# LT328v2.net
KiCad netlist of a schematic drawn in EAGLE
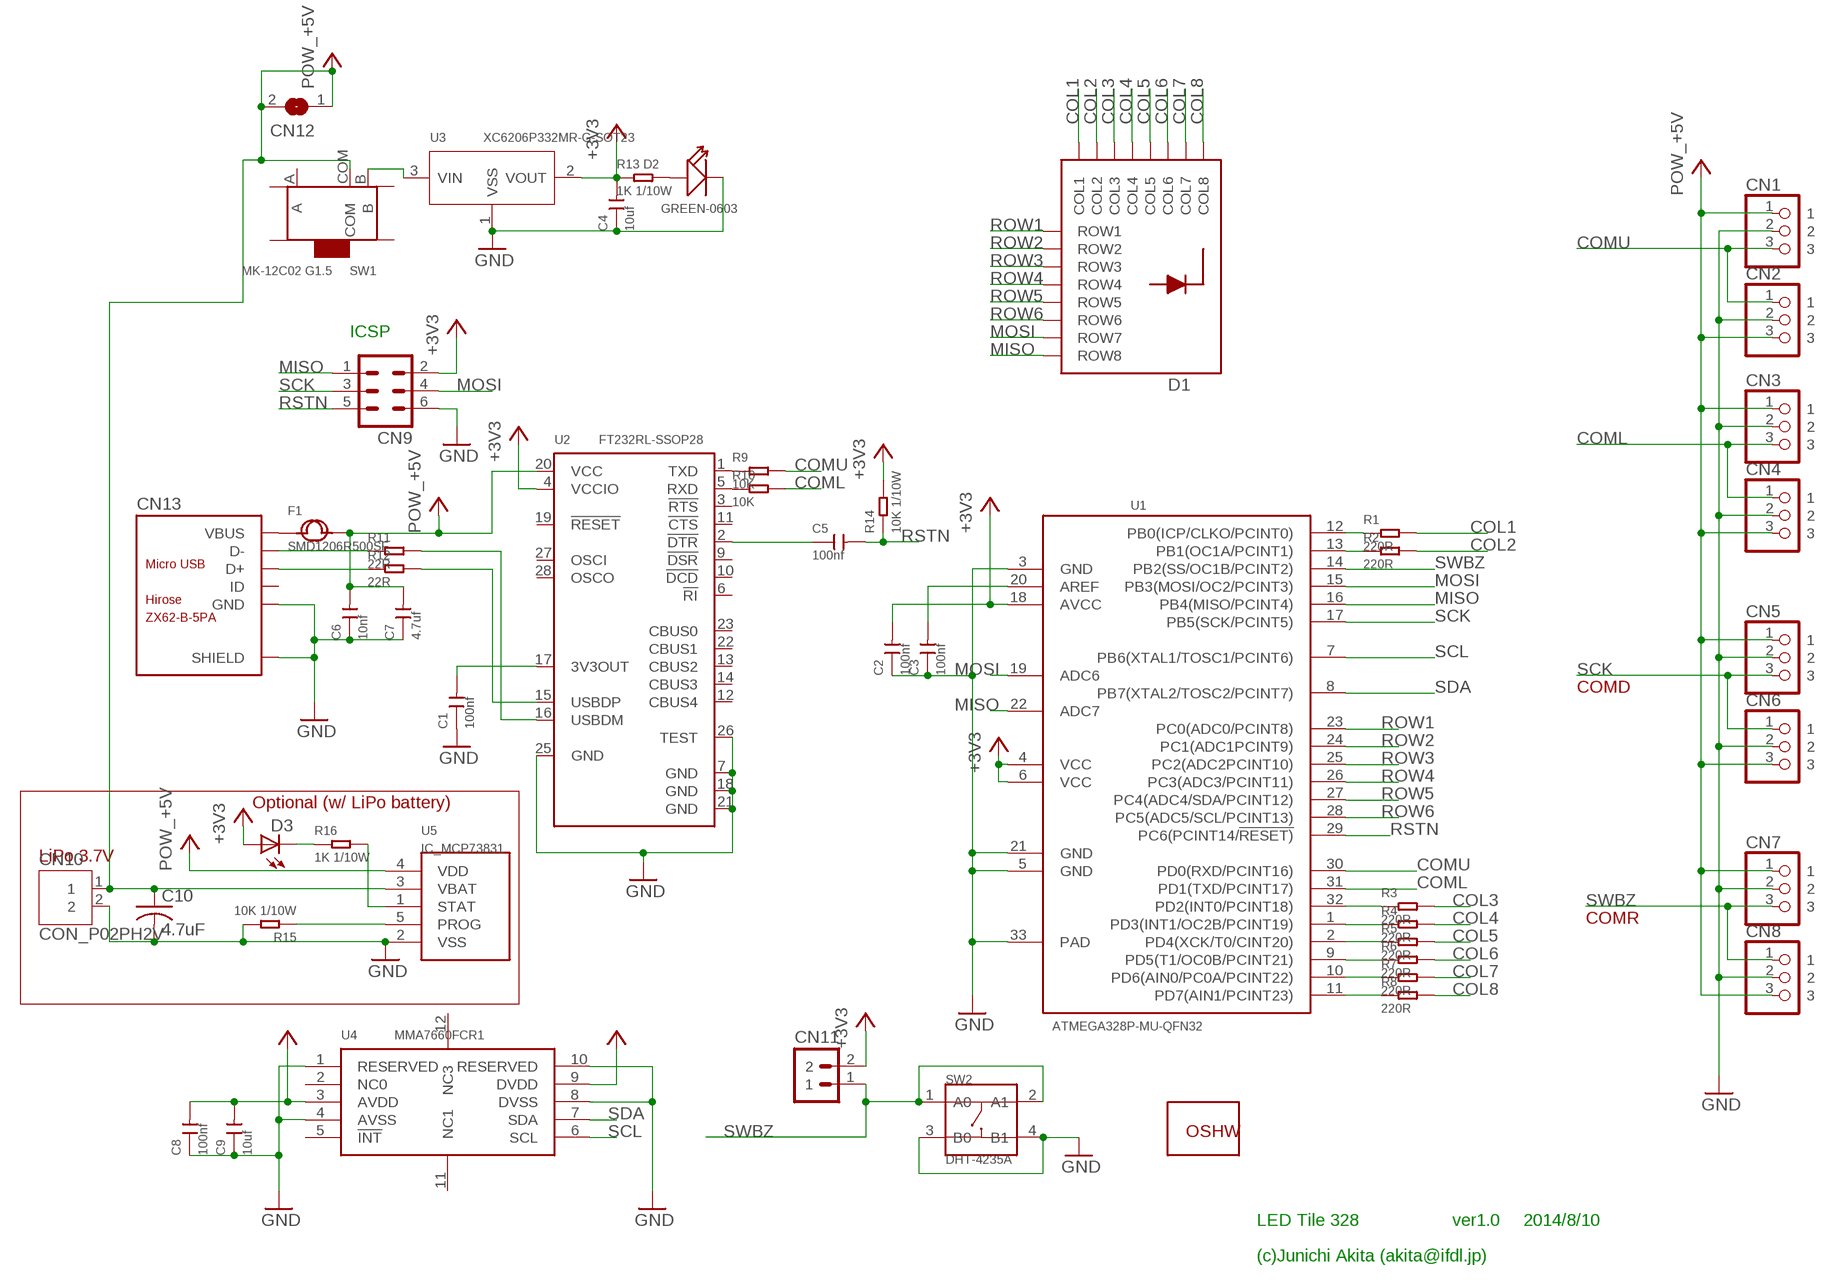
[diagram p0: schematic, sheet 1]

(export (version "E")
  (design (tool "Eeschema 10.0.6"))
  (components
    (comp (ref "C1")
      (value "100nf")
      (footprint "eagle-import:C0603")
      (fields (field (name "MPN") "CC0603KRX7R9BB104"))
      (libsource (lib "eagle-import") (part "CERAMIC-100NF-50V-10%-X7R(0603)"))
    )
    (comp (ref "C2")
      (value "100nf")
      (footprint "eagle-import:C0603")
      (fields (field (name "MPN") "CC0603KRX7R9BB104"))
      (libsource (lib "eagle-import") (part "CERAMIC-100NF-50V-10%-X7R(0603)"))
    )
    (comp (ref "C3")
      (value "100nf")
      (footprint "eagle-import:C0603")
      (fields (field (name "MPN") "CC0603KRX7R9BB104"))
      (libsource (lib "eagle-import") (part "CERAMIC-100NF-50V-10%-X7R(0603)"))
    )
    (comp (ref "C4")
      (value "10uf")
      (footprint "eagle-import:C0805")
      (fields (field (name "MPN") "CC0805ZKY5V6BB106"))
      (libsource (lib "eagle-import") (part "CERAMIC-10UF-10V-(-20%～+80%)-Y5V(0805)"))
    )
    (comp (ref "C5")
      (value "100nf")
      (footprint "eagle-import:C0603")
      (fields (field (name "MPN") "CC0603KRX7R9BB104"))
      (libsource (lib "eagle-import") (part "CERAMIC-100NF-50V-10%-X7R(0603)"))
    )
    (comp (ref "C6")
      (value "10nf")
      (footprint "eagle-import:C0603")
      (fields (field (name "MPN") "CC0603KRX7R9BB103"))
      (libsource (lib "eagle-import") (part "CERAMIC-10NF-50V-10%-X7R(0603)"))
    )
    (comp (ref "C7")
      (value "4.7uf")
      (footprint "eagle-import:C0603")
      (fields (field (name "MPN") "CC0603KRX5R6BB475"))
      (libsource (lib "eagle-import") (part "CERAMIC-4.7UF-10V-10%-X5R(0603)"))
    )
    (comp (ref "C8")
      (value "100nf")
      (footprint "eagle-import:C0603")
      (fields (field (name "MPN") "CC0603KRX7R9BB104"))
      (libsource (lib "eagle-import") (part "CERAMIC-100NF-50V-10%-X7R(0603)"))
    )
    (comp (ref "C9")
      (value "10uf")
      (footprint "eagle-import:C0805")
      (fields (field (name "MPN") "CC0805ZKY5V6BB106"))
      (libsource (lib "eagle-import") (part "CERAMIC-10UF-10V-(-20%～+80%)-Y5V(0805)"))
    )
    (comp (ref "C10")
      (value "4.7uF")
      (footprint "eagle-import:C0603")
      (libsource (lib "eagle-import") (part "C-USC0603"))
    )
    (comp (ref "CN1")
      (value "CON_PINHD-1X3R")
      (footprint "eagle-import:1X03R")
      (libsource (lib "eagle-import") (part "CON_PINHD-1X3R"))
    )
    (comp (ref "CN2")
      (value "CON_PINHD-1X3R")
      (footprint "eagle-import:1X03R")
      (libsource (lib "eagle-import") (part "CON_PINHD-1X3R"))
    )
    (comp (ref "CN3")
      (value "CON_PINHD-1X3R")
      (footprint "eagle-import:1X03R")
      (libsource (lib "eagle-import") (part "CON_PINHD-1X3R"))
    )
    (comp (ref "CN4")
      (value "CON_PINHD-1X3R")
      (footprint "eagle-import:1X03R")
      (libsource (lib "eagle-import") (part "CON_PINHD-1X3R"))
    )
    (comp (ref "CN5")
      (value "CON_PINHD-1X3R")
      (footprint "eagle-import:1X03R")
      (libsource (lib "eagle-import") (part "CON_PINHD-1X3R"))
    )
    (comp (ref "CN6")
      (value "CON_PINHD-1X3R")
      (footprint "eagle-import:1X03R")
      (libsource (lib "eagle-import") (part "CON_PINHD-1X3R"))
    )
    (comp (ref "CN7")
      (value "CON_PINHD-1X3R")
      (footprint "eagle-import:1X03R")
      (libsource (lib "eagle-import") (part "CON_PINHD-1X3R"))
    )
    (comp (ref "CN8")
      (value "CON_PINHD-1X3R")
      (footprint "eagle-import:1X03R")
      (libsource (lib "eagle-import") (part "CON_PINHD-1X3R"))
    )
    (comp (ref "CN9")
      (value "MA03-2")
      (footprint "eagle-import:MA03-2")
      (libsource (lib "eagle-import") (part "MA03-2"))
    )
    (comp (ref "CN10")
      (value "CON_P02PH2V")
      (footprint "eagle-import:JST-PH2")
      (libsource (lib "eagle-import") (part "CON_P02PH2V"))
    )
    (comp (ref "CN11")
      (value "CON_PINHD-1X2PTH")
      (footprint "eagle-import:SPARKFUN_1X02")
      (libsource (lib "eagle-import") (part "CON_PINHD-1X2PTH"))
    )
    (comp (ref "CN12")
      (value "JUMPER_SJ")
      (footprint "eagle-import:JUMPER_SJ")
      (libsource (lib "eagle-import") (part "JUMPER_SJ"))
    )
    (comp (ref "CN13")
      (value "ZX62-B-5PA")
      (footprint "eagle-import:MICRO-USB5+6P-SMD-0.65-AB")
      (libsource (lib "eagle-import") (part "MICRO-USB-SMD(ZX62-B-5PA)"))
    )
    (comp (ref "D1")
      (value "LED_OSL641501BRA")
      (footprint "eagle-import:TOM-1588BH")
      (libsource (lib "eagle-import") (part "LED_OSL641501BRA"))
    )
    (comp (ref "D2")
      (value "GREEN-0603")
      (footprint "eagle-import:LED-0603")
      (fields (field (name "MPN") "19-217-G7C-AN1P2-3T"))
      (libsource (lib "eagle-import") (part "SMD-LED-CLEAR-GREEN(0603)"))
    )
    (comp (ref "D3")
      (value "LED0603")
      (footprint "eagle-import:SPARKFUN_LED-0603")
      (libsource (lib "eagle-import") (part "LED0603"))
    )
    (comp (ref "F1")
      (value "SMD1206R500SF")
      (footprint "eagle-import:F1206")
      (libsource (lib "eagle-import") (part "SMD-PPTC-500MA(1206)"))
    )
    (comp (ref "GOLD_ORB_SM1")
      (value "OSHWLOGO_GOLD_ORB_SM")
      (footprint "eagle-import:OSHW2")
      (libsource (lib "eagle-import") (part "OSHWLOGO_GOLD_ORB_SM"))
    )
    (comp (ref "R1")
      (value "220R")
      (footprint "eagle-import:R0603")
      (fields (field (name "MPN") "RC0603JR-07220RL"))
      (libsource (lib "eagle-import") (part "SMD-RES-220R-5%-1/10W(0603)"))
    )
    (comp (ref "R2")
      (value "220R")
      (footprint "eagle-import:R0603")
      (fields (field (name "MPN") "RC0603JR-07220RL"))
      (libsource (lib "eagle-import") (part "SMD-RES-220R-5%-1/10W(0603)"))
    )
    (comp (ref "R3")
      (value "220R")
      (footprint "eagle-import:R0603")
      (fields (field (name "MPN") "RC0603JR-07220RL"))
      (libsource (lib "eagle-import") (part "SMD-RES-220R-5%-1/10W(0603)"))
    )
    (comp (ref "R4")
      (value "220R")
      (footprint "eagle-import:R0603")
      (fields (field (name "MPN") "RC0603JR-07220RL"))
      (libsource (lib "eagle-import") (part "SMD-RES-220R-5%-1/10W(0603)"))
    )
    (comp (ref "R5")
      (value "220R")
      (footprint "eagle-import:R0603")
      (fields (field (name "MPN") "RC0603JR-07220RL"))
      (libsource (lib "eagle-import") (part "SMD-RES-220R-5%-1/10W(0603)"))
    )
    (comp (ref "R6")
      (value "220R")
      (footprint "eagle-import:R0603")
      (fields (field (name "MPN") "RC0603JR-07220RL"))
      (libsource (lib "eagle-import") (part "SMD-RES-220R-5%-1/10W(0603)"))
    )
    (comp (ref "R7")
      (value "220R")
      (footprint "eagle-import:R0603")
      (fields (field (name "MPN") "RC0603JR-07220RL"))
      (libsource (lib "eagle-import") (part "SMD-RES-220R-5%-1/10W(0603)"))
    )
    (comp (ref "R8")
      (value "220R")
      (footprint "eagle-import:R0603")
      (fields (field (name "MPN") "RC0603JR-07220RL"))
      (libsource (lib "eagle-import") (part "SMD-RES-220R-5%-1/10W(0603)"))
    )
    (comp (ref "R9")
      (value "10K")
      (footprint "eagle-import:R0603")
      (fields (field (name "MPN") "RC0603FR-0710KL"))
      (libsource (lib "eagle-import") (part "SMD-RES-10K-1%-1/10W(0603)"))
    )
    (comp (ref "R10")
      (value "10K")
      (footprint "eagle-import:R0603")
      (fields (field (name "MPN") "RC0603FR-0710KL"))
      (libsource (lib "eagle-import") (part "SMD-RES-10K-1%-1/10W(0603)"))
    )
    (comp (ref "R11")
      (value "22R")
      (footprint "eagle-import:R0603")
      (fields (field (name "MPN") "RC0603JR-0722RL"))
      (libsource (lib "eagle-import") (part "SMD-RES-22R-5%-1/10W(0603)"))
    )
    (comp (ref "R12")
      (value "22R")
      (footprint "eagle-import:R0603")
      (fields (field (name "MPN") "RC0603JR-0722RL"))
      (libsource (lib "eagle-import") (part "SMD-RES-22R-5%-1/10W(0603)"))
    )
    (comp (ref "R13")
      (value "1K 1/10W")
      (footprint "eagle-import:R0603")
      (fields (field (name "MPN") "RC0603JR-071KL"))
      (libsource (lib "eagle-import") (part "SMD-RES-1K-5%-1/10W(0603)"))
    )
    (comp (ref "R14")
      (value "10K 1/10W")
      (footprint "eagle-import:R0603")
      (fields (field (name "MPN") "RC0603JR-0710KL"))
      (libsource (lib "eagle-import") (part "SMD-RES-10K-5%-1/10W(0603)"))
    )
    (comp (ref "R15")
      (value "10K 1/10W")
      (footprint "eagle-import:R0603")
      (fields (field (name "MPN") "RC0603JR-0710KL"))
      (libsource (lib "eagle-import") (part "SMD-RES-10K-5%-1/10W(0603)"))
    )
    (comp (ref "R16")
      (value "1K 1/10W")
      (footprint "eagle-import:R0603")
      (fields (field (name "MPN") "RC0603JR-071KL"))
      (libsource (lib "eagle-import") (part "SMD-RES-1K-5%-1/10W(0603)"))
    )
    (comp (ref "SW1")
      (value "MK-12C02 G1.5")
      (footprint "eagle-import:SW7-SMD-L6.7X2.7X3.2MM")
      (libsource (lib "eagle-import") (part "SMD-TOGGLE-SWITCH-ON-ON(3+4P-6.7X2.7MM)"))
    )
    (comp (ref "SW2")
      (value "DHT-4235A")
      (footprint "eagle-import:SW4-SMD-4.2X3.2X2.5MM")
      (libsource (lib "eagle-import") (part "SMD-BUTTON-TOP-DHT-4235A(4P-4.2X3.2MM)"))
    )
    (comp (ref "U1")
      (value "ATMEGA328P-MU-QFN32")
      (footprint "eagle-import:QFN32G-0.5-5X5MM")
      (fields (field (name "MPN") "ATMEGA328P-MU"))
      (libsource (lib "eagle-import") (part "MCU-ATMEGA328P-MU(QFN32)"))
    )
    (comp (ref "U2")
      (value "FT232RL-SSOP28")
      (footprint "eagle-import:SSOP28-0.65-10.2X5.2MM")
      (fields (field (name "MPN") "FT232RL"))
      (libsource (lib "eagle-import") (part "INTERFACE-FT232RL(SSOP28)"))
    )
    (comp (ref "U3")
      (value "XC6206P332MR-G-SOT23")
      (footprint "eagle-import:SOT-23")
      (fields (field (name "MPN") "XC6206P332MR-G"))
      (libsource (lib "eagle-import") (part "PMIC-LDO-XC6206P332MR-G(SOT23)"))
    )
    (comp (ref "U4")
      (value "MMA7660FCR1")
      (footprint "eagle-import:DFN10-0.5-3.0X3.0MM")
      (libsource (lib "eagle-import") (part "MOTION/POSITION-MMA7660FCR1(DFN10)"))
    )
    (comp (ref "U5")
      (value "IC_MCP73831")
      (footprint "eagle-import:SOT23-5L")
      (libsource (lib "eagle-import") (part "IC_MCP73831"))
    )
  )
  (nets
    (net (code "1") (name "+3V3") (class "Default")
      (node (ref "C2") (pin "2") (pinfunction "2_2") (pintype "passive"))
      (node (ref "C4") (pin "2") (pinfunction "2_2") (pintype "passive"))
      (node (ref "C8") (pin "2") (pinfunction "2_2") (pintype "passive"))
      (node (ref "C9") (pin "2") (pinfunction "2_2") (pintype "passive"))
      (node (ref "CN11") (pin "2") (pinfunction "2_2") (pintype "passive"))
      (node (ref "CN9") (pin "2") (pinfunction "2_2") (pintype "passive"))
      (node (ref "D3") (pin "A") (pinfunction "A_A") (pintype "passive"))
      (node (ref "R13") (pin "1") (pinfunction "1_1") (pintype "passive"))
      (node (ref "R14") (pin "2") (pinfunction "2_2") (pintype "passive"))
      (node (ref "U1") (pin "18") (pinfunction "AVCC_18") (pintype "bidirectional"))
      (node (ref "U1") (pin "4") (pinfunction "VCC_4") (pintype "bidirectional"))
      (node (ref "U1") (pin "6") (pinfunction "VCC_6") (pintype "bidirectional"))
      (node (ref "U2") (pin "4") (pinfunction "VCCIO_4") (pintype "input"))
      (node (ref "U3") (pin "2") (pinfunction "VOUT_2") (pintype "output"))
      (node (ref "U4") (pin "3") (pinfunction "AVDD_3") (pintype "power_in"))
      (node (ref "U4") (pin "9") (pinfunction "DVDD_9") (pintype "bidirectional"))
    )
    (net (code "2") (name "/COL1") (class "Default")
      (node (ref "D1") (pin "P$13") (pinfunction "COL1_P$13") (pintype "bidirectional"))
      (node (ref "R1") (pin "2") (pinfunction "2_2") (pintype "passive"))
    )
    (net (code "3") (name "/COL2") (class "Default")
      (node (ref "D1") (pin "P$3") (pinfunction "COL2_P$3") (pintype "bidirectional"))
      (node (ref "R2") (pin "2") (pinfunction "2_2") (pintype "passive"))
    )
    (net (code "4") (name "/COL3") (class "Default")
      (node (ref "D1") (pin "P$4") (pinfunction "COL3_P$4") (pintype "bidirectional"))
      (node (ref "R3") (pin "2") (pinfunction "2_2") (pintype "passive"))
    )
    (net (code "5") (name "/COL4") (class "Default")
      (node (ref "D1") (pin "P$10") (pinfunction "COL4_P$10") (pintype "bidirectional"))
      (node (ref "R4") (pin "2") (pinfunction "2_2") (pintype "passive"))
    )
    (net (code "6") (name "/COL5") (class "Default")
      (node (ref "D1") (pin "P$6") (pinfunction "COL5_P$6") (pintype "bidirectional"))
      (node (ref "R5") (pin "2") (pinfunction "2_2") (pintype "passive"))
    )
    (net (code "7") (name "/COL6") (class "Default")
      (node (ref "D1") (pin "P$11") (pinfunction "COL6_P$11") (pintype "bidirectional"))
      (node (ref "R6") (pin "2") (pinfunction "2_2") (pintype "passive"))
    )
    (net (code "8") (name "/COL7") (class "Default")
      (node (ref "D1") (pin "P$15") (pinfunction "COL7_P$15") (pintype "bidirectional"))
      (node (ref "R7") (pin "2") (pinfunction "2_2") (pintype "passive"))
    )
    (net (code "9") (name "/COL8") (class "Default")
      (node (ref "D1") (pin "P$16") (pinfunction "COL8_P$16") (pintype "bidirectional"))
      (node (ref "R8") (pin "2") (pinfunction "2_2") (pintype "passive"))
    )
    (net (code "10") (name "/COML") (class "Default")
      (node (ref "CN3") (pin "3") (pinfunction "3_3") (pintype "passive"))
      (node (ref "CN4") (pin "1") (pinfunction "1_1") (pintype "passive"))
      (node (ref "R10") (pin "2") (pinfunction "2_2") (pintype "passive"))
      (node (ref "U1") (pin "31") (pinfunction "PD1(TXD/PCINT17)_31") (pintype "bidirectional"))
    )
    (net (code "11") (name "/COMU") (class "Default")
      (node (ref "CN1") (pin "3") (pinfunction "3_3") (pintype "passive"))
      (node (ref "CN2") (pin "1") (pinfunction "1_1") (pintype "passive"))
      (node (ref "R9") (pin "2") (pinfunction "2_2") (pintype "passive"))
      (node (ref "U1") (pin "30") (pinfunction "PD0(RXD/PCINT16)_30") (pintype "bidirectional"))
    )
    (net (code "12") (name "/MISO") (class "Default")
      (node (ref "CN9") (pin "1") (pinfunction "1_1") (pintype "passive"))
      (node (ref "D1") (pin "P$5") (pinfunction "ROW8_P$5") (pintype "bidirectional"))
      (node (ref "U1") (pin "16") (pinfunction "PB4(MISO/PCINT4)_16") (pintype "bidirectional"))
      (node (ref "U1") (pin "22") (pinfunction "ADC7_22") (pintype "bidirectional"))
    )
    (net (code "13") (name "/MOSI") (class "Default")
      (node (ref "CN9") (pin "4") (pinfunction "4_4") (pintype "passive"))
      (node (ref "D1") (pin "P$2") (pinfunction "ROW7_P$2") (pintype "bidirectional"))
      (node (ref "U1") (pin "15") (pinfunction "PB3(MOSI/OC2/PCINT3)_15") (pintype "bidirectional"))
      (node (ref "U1") (pin "19") (pinfunction "ADC6_19") (pintype "bidirectional"))
    )
    (net (code "14") (name "/ROW1") (class "Default")
      (node (ref "D1") (pin "P$9") (pinfunction "ROW1_P$9") (pintype "bidirectional"))
      (node (ref "U1") (pin "23") (pinfunction "PC0(ADC0/PCINT8)_23") (pintype "bidirectional"))
    )
    (net (code "15") (name "/ROW2") (class "Default")
      (node (ref "D1") (pin "P$14") (pinfunction "ROW2_P$14") (pintype "bidirectional"))
      (node (ref "U1") (pin "24") (pinfunction "PC1(ADC1PCINT9)_24") (pintype "bidirectional"))
    )
    (net (code "16") (name "/ROW3") (class "Default")
      (node (ref "D1") (pin "P$8") (pinfunction "ROW3_P$8") (pintype "bidirectional"))
      (node (ref "U1") (pin "25") (pinfunction "PC2(ADC2PCINT10)_25") (pintype "bidirectional"))
    )
    (net (code "17") (name "/ROW4") (class "Default")
      (node (ref "D1") (pin "P$12") (pinfunction "ROW4_P$12") (pintype "bidirectional"))
      (node (ref "U1") (pin "26") (pinfunction "PC3(ADC3/PCINT11)_26") (pintype "bidirectional"))
    )
    (net (code "18") (name "/ROW5") (class "Default")
      (node (ref "D1") (pin "P$1") (pinfunction "ROW5_P$1") (pintype "bidirectional"))
      (node (ref "U1") (pin "27") (pinfunction "PC4(ADC4/SDA/PCINT12)_27") (pintype "bidirectional"))
    )
    (net (code "19") (name "/ROW6") (class "Default")
      (node (ref "D1") (pin "P$7") (pinfunction "ROW6_P$7") (pintype "bidirectional"))
      (node (ref "U1") (pin "28") (pinfunction "PC5(ADC5/SCL/PCINT13)_28") (pintype "bidirectional"))
    )
    (net (code "20") (name "/RSTN") (class "Default")
      (node (ref "C5") (pin "2") (pinfunction "2_2") (pintype "passive"))
      (node (ref "CN9") (pin "5") (pinfunction "5_5") (pintype "passive"))
      (node (ref "R14") (pin "1") (pinfunction "1_1") (pintype "passive"))
      (node (ref "U1") (pin "29") (pinfunction "PC6(PCINT14/~{RESET})_29") (pintype "bidirectional"))
    )
    (net (code "21") (name "/SCK") (class "Default")
      (node (ref "CN5") (pin "3") (pinfunction "3_3") (pintype "passive"))
      (node (ref "CN6") (pin "1") (pinfunction "1_1") (pintype "passive"))
      (node (ref "CN9") (pin "3") (pinfunction "3_3") (pintype "passive"))
      (node (ref "U1") (pin "17") (pinfunction "PB5(SCK/PCINT5)_17") (pintype "bidirectional"))
    )
    (net (code "22") (name "/SCL") (class "Default")
      (node (ref "U1") (pin "7") (pinfunction "PB6(XTAL1/TOSC1/PCINT6)_7") (pintype "bidirectional"))
      (node (ref "U4") (pin "6") (pinfunction "SCL_6") (pintype "bidirectional"))
    )
    (net (code "23") (name "/SDA") (class "Default")
      (node (ref "U1") (pin "8") (pinfunction "PB7(XTAL2/TOSC2/PCINT7)_8") (pintype "bidirectional"))
      (node (ref "U4") (pin "7") (pinfunction "SDA_7") (pintype "bidirectional"))
    )
    (net (code "24") (name "/SWBZ") (class "Default")
      (node (ref "CN11") (pin "1") (pinfunction "1_1") (pintype "passive"))
      (node (ref "CN7") (pin "3") (pinfunction "3_3") (pintype "passive"))
      (node (ref "CN8") (pin "1") (pinfunction "1_1") (pintype "passive"))
      (node (ref "SW2") (pin "1") (pinfunction "A0_1") (pintype "bidirectional"))
      (node (ref "SW2") (pin "2") (pinfunction "A1_2") (pintype "bidirectional"))
      (node (ref "U1") (pin "14") (pinfunction "PB2(SS/OC1B/PCINT2)_14") (pintype "bidirectional"))
    )
    (net (code "25") (name "GND") (class "Default")
      (node (ref "C1") (pin "1") (pinfunction "1_1") (pintype "passive"))
      (node (ref "C10") (pin "2") (pinfunction "2_2") (pintype "passive"))
      (node (ref "C2") (pin "1") (pinfunction "1_1") (pintype "passive"))
      (node (ref "C3") (pin "1") (pinfunction "1_1") (pintype "passive"))
      (node (ref "C4") (pin "1") (pinfunction "1_1") (pintype "passive"))
      (node (ref "C6") (pin "1") (pinfunction "1_1") (pintype "passive"))
      (node (ref "C7") (pin "1") (pinfunction "1_1") (pintype "passive"))
      (node (ref "C8") (pin "1") (pinfunction "1_1") (pintype "passive"))
      (node (ref "C9") (pin "1") (pinfunction "1_1") (pintype "passive"))
      (node (ref "CN1") (pin "2") (pinfunction "2_2") (pintype "passive"))
      (node (ref "CN10") (pin "2") (pinfunction "2_2") (pintype "passive"))
      (node (ref "CN13") (pin "5") (pinfunction "GND_5") (pintype "power_in"))
      (node (ref "CN13") (pin "P1") (pinfunction "SHIELD_P1") (pintype "power_in"))
      (node (ref "CN13") (pin "P2") (pinfunction "SHIELD_P2") (pintype "power_in"))
      (node (ref "CN13") (pin "P3") (pinfunction "SHIELD_P3") (pintype "power_in"))
      (node (ref "CN13") (pin "P4") (pinfunction "SHIELD_P4") (pintype "power_in"))
      (node (ref "CN13") (pin "P5") (pinfunction "SHIELD_P5") (pintype "power_in"))
      (node (ref "CN13") (pin "P6") (pinfunction "SHIELD_P6") (pintype "power_in"))
      (node (ref "CN2") (pin "2") (pinfunction "2_2") (pintype "passive"))
      (node (ref "CN3") (pin "2") (pinfunction "2_2") (pintype "passive"))
      (node (ref "CN4") (pin "2") (pinfunction "2_2") (pintype "passive"))
      (node (ref "CN5") (pin "2") (pinfunction "2_2") (pintype "passive"))
      (node (ref "CN6") (pin "2") (pinfunction "2_2") (pintype "passive"))
      (node (ref "CN7") (pin "2") (pinfunction "2_2") (pintype "passive"))
      (node (ref "CN8") (pin "2") (pinfunction "2_2") (pintype "passive"))
      (node (ref "CN9") (pin "6") (pinfunction "6_6") (pintype "passive"))
      (node (ref "D2") (pin "-") (pinfunction "-_-") (pintype "passive"))
      (node (ref "R15") (pin "2") (pinfunction "2_2") (pintype "passive"))
      (node (ref "SW2") (pin "3") (pinfunction "B0_3") (pintype "bidirectional"))
      (node (ref "SW2") (pin "4") (pinfunction "B1_4") (pintype "bidirectional"))
      (node (ref "U1") (pin "21") (pinfunction "GND_21") (pintype "bidirectional"))
      (node (ref "U1") (pin "3") (pinfunction "GND_3") (pintype "bidirectional"))
      (node (ref "U1") (pin "33") (pinfunction "PAD_33") (pintype "bidirectional"))
      (node (ref "U1") (pin "5") (pinfunction "GND_5") (pintype "bidirectional"))
      (node (ref "U2") (pin "18") (pinfunction "GND_18") (pintype "input"))
      (node (ref "U2") (pin "21") (pinfunction "GND_21") (pintype "input"))
      (node (ref "U2") (pin "25") (pinfunction "GND_25") (pintype "input"))
      (node (ref "U2") (pin "26") (pinfunction "TEST_26") (pintype "input"))
      (node (ref "U2") (pin "7") (pinfunction "GND_7") (pintype "input"))
      (node (ref "U3") (pin "1") (pinfunction "VSS_1") (pintype "power_in"))
      (node (ref "U4") (pin "1") (pinfunction "RESERVED_1") (pintype "bidirectional"))
      (node (ref "U4") (pin "10") (pinfunction "RESERVED_10") (pintype "bidirectional"))
      (node (ref "U4") (pin "4") (pinfunction "AVSS_4") (pintype "power_in"))
      (node (ref "U4") (pin "8") (pinfunction "DVSS_8") (pintype "bidirectional"))
      (node (ref "U5") (pin "2") (pinfunction "VSS_2") (pintype "bidirectional"))
    )
    (net (code "26") (name "Net-(CN13-D+)") (class "Default")
      (node (ref "CN13") (pin "3") (pinfunction "D+_3") (pintype "bidirectional"))
      (node (ref "R12") (pin "1") (pinfunction "1_1") (pintype "passive"))
    )
    (net (code "27") (name "Net-(CN13-D-)") (class "Default")
      (node (ref "CN13") (pin "2") (pinfunction "D-_2") (pintype "bidirectional"))
      (node (ref "R11") (pin "1") (pinfunction "1_1") (pintype "passive"))
    )
    (net (code "28") (name "Net-(CN13-VBUS)") (class "Default")
      (node (ref "CN13") (pin "1") (pinfunction "VBUS_1") (pintype "power_in"))
      (node (ref "F1") (pin "1") (pinfunction "1_1") (pintype "bidirectional"))
    )
    (net (code "29") (name "Net-(D2-Pad+)") (class "Default")
      (node (ref "D2") (pin "+") (pinfunction "+_+") (pintype "passive"))
      (node (ref "R13") (pin "2") (pinfunction "2_2") (pintype "passive"))
    )
    (net (code "30") (name "Net-(D3-PadC)") (class "Default")
      (node (ref "D3") (pin "C") (pinfunction "C_C") (pintype "passive"))
      (node (ref "R16") (pin "1") (pinfunction "1_1") (pintype "passive"))
    )
    (net (code "31") (name "Net-(U1-AREF)") (class "Default")
      (node (ref "C3") (pin "2") (pinfunction "2_2") (pintype "passive"))
      (node (ref "U1") (pin "20") (pinfunction "AREF_20") (pintype "bidirectional"))
    )
    (net (code "32") (name "Net-(U1-PB0(ICP{slash}CLKO{slash}PCINT0))") (class "Default")
      (node (ref "R1") (pin "1") (pinfunction "1_1") (pintype "passive"))
      (node (ref "U1") (pin "12") (pinfunction "PB0(ICP/CLKO/PCINT0)_12") (pintype "bidirectional"))
    )
    (net (code "33") (name "Net-(U1-PB1(OC1A{slash}PCINT1))") (class "Default")
      (node (ref "R2") (pin "1") (pinfunction "1_1") (pintype "passive"))
      (node (ref "U1") (pin "13") (pinfunction "PB1(OC1A/PCINT1)_13") (pintype "bidirectional"))
    )
    (net (code "34") (name "Net-(U1-PD2(INT0{slash}PCINT18))") (class "Default")
      (node (ref "R3") (pin "1") (pinfunction "1_1") (pintype "passive"))
      (node (ref "U1") (pin "32") (pinfunction "PD2(INT0/PCINT18)_32") (pintype "bidirectional"))
    )
    (net (code "35") (name "Net-(U1-PD3(INT1{slash}OC2B{slash}PCINT19))") (class "Default")
      (node (ref "R4") (pin "1") (pinfunction "1_1") (pintype "passive"))
      (node (ref "U1") (pin "1") (pinfunction "PD3(INT1/OC2B/PCINT19)_1") (pintype "bidirectional"))
    )
    (net (code "36") (name "Net-(U1-PD4(XCK{slash}T0{slash}CINT20))") (class "Default")
      (node (ref "R5") (pin "1") (pinfunction "1_1") (pintype "passive"))
      (node (ref "U1") (pin "2") (pinfunction "PD4(XCK/T0/CINT20)_2") (pintype "bidirectional"))
    )
    (net (code "37") (name "Net-(U1-PD5(T1{slash}OC0B{slash}PCINT21))") (class "Default")
      (node (ref "R6") (pin "1") (pinfunction "1_1") (pintype "passive"))
      (node (ref "U1") (pin "9") (pinfunction "PD5(T1/OC0B/PCINT21)_9") (pintype "bidirectional"))
    )
    (net (code "38") (name "Net-(U1-PD6(AIN0{slash}PC0A{slash}PCINT22))") (class "Default")
      (node (ref "R7") (pin "1") (pinfunction "1_1") (pintype "passive"))
      (node (ref "U1") (pin "10") (pinfunction "PD6(AIN0/PC0A/PCINT22)_10") (pintype "bidirectional"))
    )
    (net (code "39") (name "Net-(U1-PD7(AIN1{slash}PCINT23))") (class "Default")
      (node (ref "R8") (pin "1") (pinfunction "1_1") (pintype "passive"))
      (node (ref "U1") (pin "11") (pinfunction "PD7(AIN1/PCINT23)_11") (pintype "bidirectional"))
    )
    (net (code "40") (name "Net-(U2-3V3OUT)") (class "Default")
      (node (ref "C1") (pin "2") (pinfunction "2_2") (pintype "passive"))
      (node (ref "U2") (pin "17") (pinfunction "3V3OUT_17") (pintype "input"))
    )
    (net (code "41") (name "Net-(U2-RXD)") (class "Default")
      (node (ref "R10") (pin "1") (pinfunction "1_1") (pintype "passive"))
      (node (ref "U2") (pin "5") (pinfunction "RXD_5") (pintype "input"))
    )
    (net (code "42") (name "Net-(U2-TXD)") (class "Default")
      (node (ref "R9") (pin "1") (pinfunction "1_1") (pintype "passive"))
      (node (ref "U2") (pin "1") (pinfunction "TXD_1") (pintype "input"))
    )
    (net (code "43") (name "Net-(U2-USBDM)") (class "Default")
      (node (ref "R11") (pin "2") (pinfunction "2_2") (pintype "passive"))
      (node (ref "U2") (pin "16") (pinfunction "USBDM_16") (pintype "input"))
    )
    (net (code "44") (name "Net-(U2-USBDP)") (class "Default")
      (node (ref "R12") (pin "2") (pinfunction "2_2") (pintype "passive"))
      (node (ref "U2") (pin "15") (pinfunction "USBDP_15") (pintype "input"))
    )
    (net (code "45") (name "Net-(U2-~{DTR})") (class "Default")
      (node (ref "C5") (pin "1") (pinfunction "1_1") (pintype "passive"))
      (node (ref "U2") (pin "2") (pinfunction "~{DTR}_2") (pintype "input"))
    )
    (net (code "46") (name "Net-(U3-VIN)") (class "Default")
      (node (ref "SW1") (pin "B") (pinfunction "B_B") (pintype "bidirectional"))
      (node (ref "U3") (pin "3") (pinfunction "VIN_3") (pintype "input"))
    )
    (net (code "47") (name "Net-(U5-PROG)") (class "Default")
      (node (ref "R15") (pin "1") (pinfunction "1_1") (pintype "passive"))
      (node (ref "U5") (pin "5") (pinfunction "PROG_5") (pintype "bidirectional"))
    )
    (net (code "48") (name "Net-(U5-STAT)") (class "Default")
      (node (ref "R16") (pin "2") (pinfunction "2_2") (pintype "passive"))
      (node (ref "U5") (pin "1") (pinfunction "STAT_1") (pintype "bidirectional"))
    )
    (net (code "49") (name "POW_+5V") (class "Default")
      (node (ref "C10") (pin "1") (pinfunction "1_1") (pintype "passive"))
      (node (ref "C6") (pin "2") (pinfunction "2_2") (pintype "passive"))
      (node (ref "C7") (pin "2") (pinfunction "2_2") (pintype "passive"))
      (node (ref "CN1") (pin "1") (pinfunction "1_1") (pintype "passive"))
      (node (ref "CN10") (pin "1") (pinfunction "1_1") (pintype "passive"))
      (node (ref "CN12") (pin "1") (pinfunction "1_1") (pintype "passive"))
      (node (ref "CN12") (pin "2") (pinfunction "2_2") (pintype "passive"))
      (node (ref "CN2") (pin "3") (pinfunction "3_3") (pintype "passive"))
      (node (ref "CN3") (pin "1") (pinfunction "1_1") (pintype "passive"))
      (node (ref "CN4") (pin "3") (pinfunction "3_3") (pintype "passive"))
      (node (ref "CN5") (pin "1") (pinfunction "1_1") (pintype "passive"))
      (node (ref "CN6") (pin "3") (pinfunction "3_3") (pintype "passive"))
      (node (ref "CN7") (pin "1") (pinfunction "1_1") (pintype "passive"))
      (node (ref "CN8") (pin "3") (pinfunction "3_3") (pintype "passive"))
      (node (ref "F1") (pin "2") (pinfunction "2_2") (pintype "bidirectional"))
      (node (ref "SW1") (pin "COM") (pinfunction "COM_COM") (pintype "bidirectional"))
      (node (ref "U2") (pin "20") (pinfunction "VCC_20") (pintype "input"))
      (node (ref "U5") (pin "3") (pinfunction "VBAT_3") (pintype "bidirectional"))
      (node (ref "U5") (pin "4") (pinfunction "VDD_4") (pintype "bidirectional"))
    )
    (net (code "50") (name "unconnected-(CN13-ID-Pad4)") (class "Default")
      (node (ref "CN13") (pin "4") (pinfunction "ID_4") (pintype "bidirectional"))
    )
    (net (code "51") (name "unconnected-(SW1-PadA)") (class "Default")
      (node (ref "SW1") (pin "A") (pinfunction "A_A") (pintype "bidirectional"))
    )
    (net (code "52") (name "unconnected-(SW1-PadSS1)") (class "Default")
      (node (ref "SW1") (pin "SS1") (pinfunction "SS1_SS1") (pintype "bidirectional"))
    )
    (net (code "53") (name "unconnected-(SW1-PadSS2)") (class "Default")
      (node (ref "SW1") (pin "SS2") (pinfunction "SS2_SS2") (pintype "bidirectional"))
    )
    (net (code "54") (name "unconnected-(SW1-PadSS3)") (class "Default")
      (node (ref "SW1") (pin "SS3") (pinfunction "SS3_SS3") (pintype "bidirectional"))
    )
    (net (code "55") (name "unconnected-(SW1-PadSS4)") (class "Default")
      (node (ref "SW1") (pin "SS4") (pinfunction "SS4_SS4") (pintype "bidirectional"))
    )
    (net (code "56") (name "unconnected-(U2-CBUS0-Pad23)") (class "Default")
      (node (ref "U2") (pin "23") (pinfunction "CBUS0_23") (pintype "input"))
    )
    (net (code "57") (name "unconnected-(U2-CBUS1-Pad22)") (class "Default")
      (node (ref "U2") (pin "22") (pinfunction "CBUS1_22") (pintype "input"))
    )
    (net (code "58") (name "unconnected-(U2-CBUS2-Pad13)") (class "Default")
      (node (ref "U2") (pin "13") (pinfunction "CBUS2_13") (pintype "input"))
    )
    (net (code "59") (name "unconnected-(U2-CBUS3-Pad14)") (class "Default")
      (node (ref "U2") (pin "14") (pinfunction "CBUS3_14") (pintype "input"))
    )
    (net (code "60") (name "unconnected-(U2-CBUS4-Pad12)") (class "Default")
      (node (ref "U2") (pin "12") (pinfunction "CBUS4_12") (pintype "input"))
    )
    (net (code "61") (name "unconnected-(U2-OSCI-Pad27)") (class "Default")
      (node (ref "U2") (pin "27") (pinfunction "OSCI_27") (pintype "input"))
    )
    (net (code "62") (name "unconnected-(U2-OSCO-Pad28)") (class "Default")
      (node (ref "U2") (pin "28") (pinfunction "OSCO_28") (pintype "input"))
    )
    (net (code "63") (name "unconnected-(U2-~{CTS}-Pad11)") (class "Default")
      (node (ref "U2") (pin "11") (pinfunction "~{CTS}_11") (pintype "input"))
    )
    (net (code "64") (name "unconnected-(U2-~{DCD}-Pad10)") (class "Default")
      (node (ref "U2") (pin "10") (pinfunction "~{DCD}_10") (pintype "input"))
    )
    (net (code "65") (name "unconnected-(U2-~{DSR}-Pad9)") (class "Default")
      (node (ref "U2") (pin "9") (pinfunction "~{DSR}_9") (pintype "input"))
    )
    (net (code "66") (name "unconnected-(U2-~{RESET}-Pad19)") (class "Default")
      (node (ref "U2") (pin "19") (pinfunction "~{RESET}_19") (pintype "input"))
    )
    (net (code "67") (name "unconnected-(U2-~{RI}-Pad6)") (class "Default")
      (node (ref "U2") (pin "6") (pinfunction "~{RI}_6") (pintype "input"))
    )
    (net (code "68") (name "unconnected-(U2-~{RTS}-Pad3)") (class "Default")
      (node (ref "U2") (pin "3") (pinfunction "~{RTS}_3") (pintype "input"))
    )
    (net (code "69") (name "unconnected-(U4-NC0-Pad2)") (class "Default")
      (node (ref "U4") (pin "2") (pinfunction "NC0_2") (pintype "no_connect"))
    )
    (net (code "70") (name "unconnected-(U4-NC1-Pad11)") (class "Default")
      (node (ref "U4") (pin "11") (pinfunction "NC1_11") (pintype "no_connect"))
    )
    (net (code "71") (name "unconnected-(U4-NC3-Pad12)") (class "Default")
      (node (ref "U4") (pin "12") (pinfunction "NC3_12") (pintype "no_connect"))
    )
    (net (code "72") (name "unconnected-(U4-~{INT}-Pad5)") (class "Default")
      (node (ref "U4") (pin "5") (pinfunction "~{INT}_5") (pintype "bidirectional"))
    )
  )
)
